# front_panel.net
KiCad netlist of a schematic drawn in EAGLE
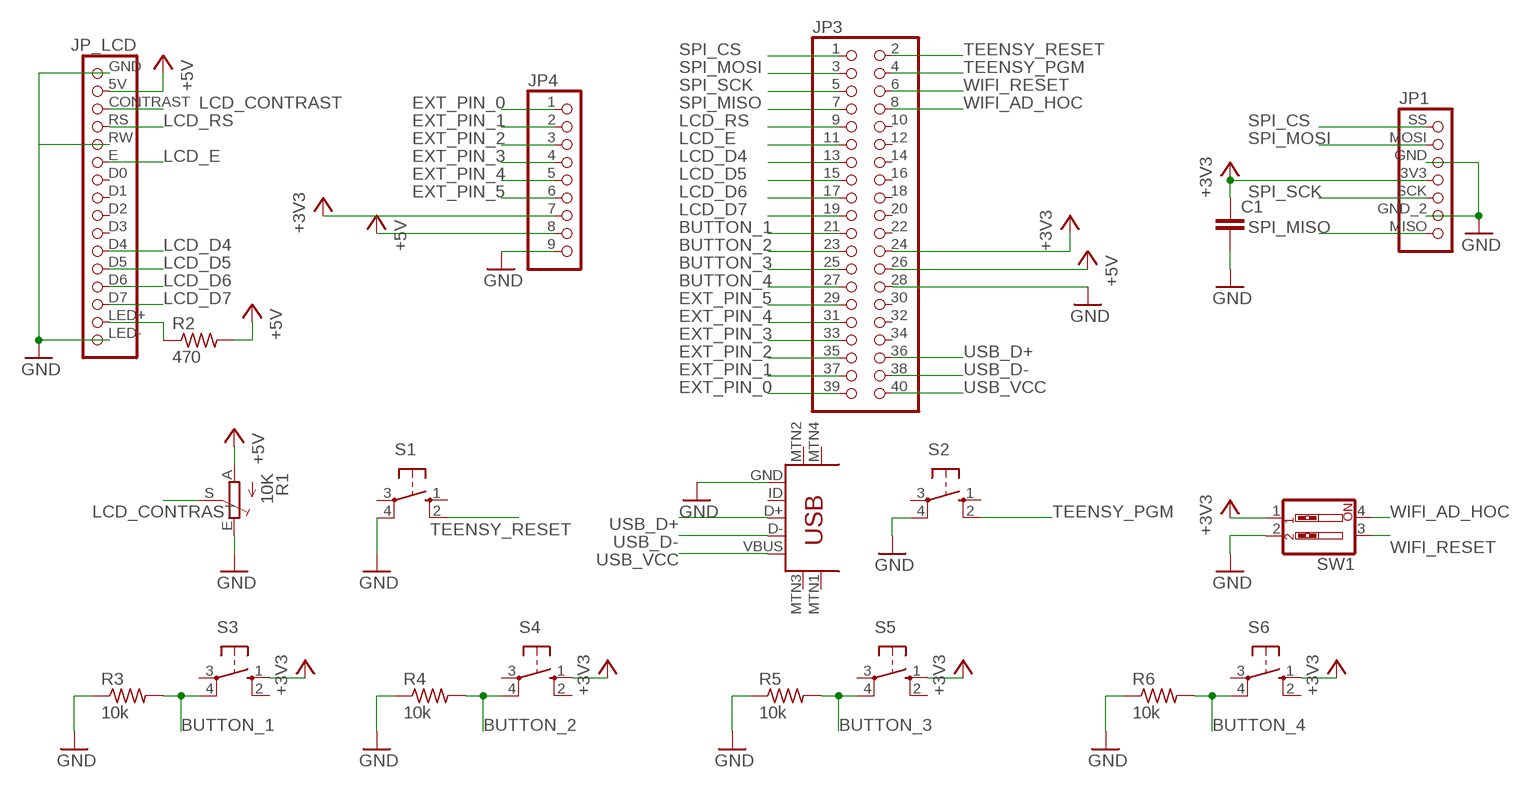
[diagram p0: schematic, sheet 1]

(export (version "E")
  (design (tool "Eeschema 10.0.6"))
  (components
    (comp (ref "C1")
      (value "0.1UF-50V-20%(PTH)KIT-EZ")
      (footprint "eagle-import:CAP-PTH-SMALL-KIT")
      (libsource (lib "eagle-import") (part "0.1UF-50V-20%(PTH)KIT-EZ"))
    )
    (comp (ref "JP1")
      (value "PINHD-1X7")
      (footprint "eagle-import:1X07")
      (libsource (lib "eagle-import") (part "PINHD-1X7"))
    )
    (comp (ref "JP3")
      (value "PINHD-2X20")
      (footprint "eagle-import:2X20")
      (libsource (lib "eagle-import") (part "PINHD-2X20"))
    )
    (comp (ref "JP4")
      (value "PINHD-1X9")
      (footprint "eagle-import:1X09")
      (libsource (lib "eagle-import") (part "PINHD-1X9"))
    )
    (comp (ref "JP_LCD")
      (value "PINHD-1X16")
      (footprint "eagle-import:1X16")
      (libsource (lib "eagle-import") (part "PINHD-1X16"))
    )
    (comp (ref "R1")
      (value "10K")
      (footprint "eagle-import:CA6V")
      (libsource (lib "eagle-import") (part "TRIM_EU-CA6V"))
    )
    (comp (ref "R2")
      (value "470")
      (footprint "eagle-import:0207_10")
      (libsource (lib "eagle-import") (part "R-US_0207/10"))
    )
    (comp (ref "R3")
      (value "10k")
      (footprint "eagle-import:0207_10")
      (libsource (lib "eagle-import") (part "R-US_0207/10"))
    )
    (comp (ref "R4")
      (value "10k")
      (footprint "eagle-import:0207_10")
      (libsource (lib "eagle-import") (part "R-US_0207/10"))
    )
    (comp (ref "R5")
      (value "10k")
      (footprint "eagle-import:0207_10")
      (libsource (lib "eagle-import") (part "R-US_0207/10"))
    )
    (comp (ref "R6")
      (value "10k")
      (footprint "eagle-import:0207_10")
      (libsource (lib "eagle-import") (part "R-US_0207/10"))
    )
    (comp (ref "S1")
      (value "10-XX")
      (footprint "eagle-import:B3F-10XX")
      (fields (field (name "MPN") "B3F-1000"))
      (libsource (lib "eagle-import") (part "10-XX"))
    )
    (comp (ref "S2")
      (value "10-XX")
      (footprint "eagle-import:B3F-10XX")
      (fields (field (name "MPN") "B3F-1000"))
      (libsource (lib "eagle-import") (part "10-XX"))
    )
    (comp (ref "S3")
      (value "10-XX")
      (footprint "eagle-import:B3F-10XX")
      (fields (field (name "MPN") "B3F-1000"))
      (libsource (lib "eagle-import") (part "10-XX"))
    )
    (comp (ref "S4")
      (value "10-XX")
      (footprint "eagle-import:B3F-10XX")
      (fields (field (name "MPN") "B3F-1000"))
      (libsource (lib "eagle-import") (part "10-XX"))
    )
    (comp (ref "S5")
      (value "10-XX")
      (footprint "eagle-import:B3F-10XX")
      (fields (field (name "MPN") "B3F-1000"))
      (libsource (lib "eagle-import") (part "10-XX"))
    )
    (comp (ref "S6")
      (value "10-XX")
      (footprint "eagle-import:B3F-10XX")
      (fields (field (name "MPN") "B3F-1000"))
      (libsource (lib "eagle-import") (part "10-XX"))
    )
    (comp (ref "SW1")
      (value "SW_DIP-2")
      (footprint "eagle-import:EDG-02")
      (libsource (lib "eagle-import") (part "SW_DIP-2"))
    )
    (comp (ref "U$1")
      (value "USB-MINIB-5PIN")
      (footprint "eagle-import:USB-MINIB")
      (libsource (lib "eagle-import") (part "USB-MINIB-5PIN"))
    )
  )
  (nets
    (net (code "1") (name "+3V3") (class "Default")
      (node (ref "C1") (pin "1") (pinfunction "1_1") (pintype "passive"))
      (node (ref "JP1") (pin "3V3") (pinfunction "4_3V3") (pintype "passive"))
      (node (ref "JP3") (pin "24") (pinfunction "24_24") (pintype "passive"))
      (node (ref "JP4") (pin "7") (pinfunction "7_7") (pintype "passive"))
      (node (ref "S3") (pin "1") (pinfunction "S_1") (pintype "passive"))
      (node (ref "S4") (pin "1") (pinfunction "S_1") (pintype "passive"))
      (node (ref "S5") (pin "1") (pinfunction "S_1") (pintype "passive"))
      (node (ref "S6") (pin "1") (pinfunction "S_1") (pintype "passive"))
      (node (ref "SW1") (pin "1") (pinfunction "1_1") (pintype "passive"))
    )
    (net (code "2") (name "+5V") (class "Default")
      (node (ref "JP3") (pin "26") (pinfunction "26_26") (pintype "passive"))
      (node (ref "JP4") (pin "8") (pinfunction "8_8") (pintype "passive"))
      (node (ref "JP_LCD") (pin "5V") (pinfunction "5V_5V") (pintype "passive"))
      (node (ref "R1") (pin "A") (pinfunction "A_A") (pintype "passive"))
      (node (ref "R2") (pin "2") (pinfunction "2_2") (pintype "passive"))
    )
    (net (code "3") (name "/BUTTON_1") (class "Default")
      (node (ref "JP3") (pin "21") (pinfunction "21_21") (pintype "passive"))
      (node (ref "R3") (pin "2") (pinfunction "2_2") (pintype "passive"))
      (node (ref "S3") (pin "4") (pinfunction "P1_4") (pintype "passive"))
    )
    (net (code "4") (name "/BUTTON_2") (class "Default")
      (node (ref "JP3") (pin "23") (pinfunction "23_23") (pintype "passive"))
      (node (ref "R4") (pin "2") (pinfunction "2_2") (pintype "passive"))
      (node (ref "S4") (pin "4") (pinfunction "P1_4") (pintype "passive"))
    )
    (net (code "5") (name "/BUTTON_3") (class "Default")
      (node (ref "JP3") (pin "25") (pinfunction "25_25") (pintype "passive"))
      (node (ref "R5") (pin "2") (pinfunction "2_2") (pintype "passive"))
      (node (ref "S5") (pin "4") (pinfunction "P1_4") (pintype "passive"))
    )
    (net (code "6") (name "/BUTTON_4") (class "Default")
      (node (ref "JP3") (pin "27") (pinfunction "27_27") (pintype "passive"))
      (node (ref "R6") (pin "2") (pinfunction "2_2") (pintype "passive"))
      (node (ref "S6") (pin "4") (pinfunction "P1_4") (pintype "passive"))
    )
    (net (code "7") (name "/EXT_PIN_0") (class "Default")
      (node (ref "JP3") (pin "39") (pinfunction "39_39") (pintype "passive"))
      (node (ref "JP4") (pin "1") (pinfunction "1_1") (pintype "passive"))
    )
    (net (code "8") (name "/EXT_PIN_1") (class "Default")
      (node (ref "JP3") (pin "37") (pinfunction "37_37") (pintype "passive"))
      (node (ref "JP4") (pin "2") (pinfunction "2_2") (pintype "passive"))
    )
    (net (code "9") (name "/EXT_PIN_2") (class "Default")
      (node (ref "JP3") (pin "35") (pinfunction "35_35") (pintype "passive"))
      (node (ref "JP4") (pin "3") (pinfunction "3_3") (pintype "passive"))
    )
    (net (code "10") (name "/EXT_PIN_3") (class "Default")
      (node (ref "JP3") (pin "33") (pinfunction "33_33") (pintype "passive"))
      (node (ref "JP4") (pin "4") (pinfunction "4_4") (pintype "passive"))
    )
    (net (code "11") (name "/EXT_PIN_4") (class "Default")
      (node (ref "JP3") (pin "31") (pinfunction "31_31") (pintype "passive"))
      (node (ref "JP4") (pin "5") (pinfunction "5_5") (pintype "passive"))
    )
    (net (code "12") (name "/EXT_PIN_5") (class "Default")
      (node (ref "JP3") (pin "29") (pinfunction "29_29") (pintype "passive"))
      (node (ref "JP4") (pin "6") (pinfunction "6_6") (pintype "passive"))
    )
    (net (code "13") (name "/LCD_CONTRAST") (class "Default")
      (node (ref "JP_LCD") (pin "CONTRAST") (pinfunction "CONTRAST_CONTRAST") (pintype "passive"))
      (node (ref "R1") (pin "S") (pinfunction "S_S") (pintype "passive"))
    )
    (net (code "14") (name "/LCD_D4") (class "Default")
      (node (ref "JP3") (pin "13") (pinfunction "13_13") (pintype "passive"))
      (node (ref "JP_LCD") (pin "D4") (pinfunction "D4_D4") (pintype "passive"))
    )
    (net (code "15") (name "/LCD_D5") (class "Default")
      (node (ref "JP3") (pin "15") (pinfunction "15_15") (pintype "passive"))
      (node (ref "JP_LCD") (pin "D5") (pinfunction "D5_D5") (pintype "passive"))
    )
    (net (code "16") (name "/LCD_D6") (class "Default")
      (node (ref "JP3") (pin "17") (pinfunction "17_17") (pintype "passive"))
      (node (ref "JP_LCD") (pin "D6") (pinfunction "D6_D6") (pintype "passive"))
    )
    (net (code "17") (name "/LCD_D7") (class "Default")
      (node (ref "JP3") (pin "19") (pinfunction "19_19") (pintype "passive"))
      (node (ref "JP_LCD") (pin "D7") (pinfunction "D7_D7") (pintype "passive"))
    )
    (net (code "18") (name "/LCD_E") (class "Default")
      (node (ref "JP3") (pin "11") (pinfunction "11_11") (pintype "passive"))
      (node (ref "JP_LCD") (pin "E") (pinfunction "E_E") (pintype "passive"))
    )
    (net (code "19") (name "/LCD_RS") (class "Default")
      (node (ref "JP3") (pin "9") (pinfunction "9_9") (pintype "passive"))
      (node (ref "JP_LCD") (pin "RS") (pinfunction "RS_RS") (pintype "passive"))
    )
    (net (code "20") (name "/SPI_CS") (class "Default")
      (node (ref "JP1") (pin "SS") (pinfunction "1_SS") (pintype "passive"))
      (node (ref "JP3") (pin "1") (pinfunction "1_1") (pintype "passive"))
    )
    (net (code "21") (name "/SPI_MISO") (class "Default")
      (node (ref "JP1") (pin "MISO") (pinfunction "7_MISO") (pintype "passive"))
      (node (ref "JP3") (pin "7") (pinfunction "7_7") (pintype "passive"))
    )
    (net (code "22") (name "/SPI_MOSI") (class "Default")
      (node (ref "JP1") (pin "MOSI") (pinfunction "2_MOSI") (pintype "passive"))
      (node (ref "JP3") (pin "3") (pinfunction "3_3") (pintype "passive"))
    )
    (net (code "23") (name "/SPI_SCK") (class "Default")
      (node (ref "JP1") (pin "SCK") (pinfunction "5_SCK") (pintype "passive"))
      (node (ref "JP3") (pin "5") (pinfunction "5_5") (pintype "passive"))
    )
    (net (code "24") (name "/TEENSY_PGM") (class "Default")
      (node (ref "JP3") (pin "4") (pinfunction "4_4") (pintype "passive"))
      (node (ref "S2") (pin "2") (pinfunction "S1_2") (pintype "passive"))
    )
    (net (code "25") (name "/TEENSY_RESET") (class "Default")
      (node (ref "JP3") (pin "2") (pinfunction "2_2") (pintype "passive"))
      (node (ref "S1") (pin "2") (pinfunction "S1_2") (pintype "passive"))
    )
    (net (code "26") (name "/USB_D+") (class "Default")
      (node (ref "JP3") (pin "36") (pinfunction "36_36") (pintype "passive"))
      (node (ref "U$1") (pin "D+") (pinfunction "D+_D+") (pintype "bidirectional"))
    )
    (net (code "27") (name "/USB_D-") (class "Default")
      (node (ref "JP3") (pin "38") (pinfunction "38_38") (pintype "passive"))
      (node (ref "U$1") (pin "D-") (pinfunction "D-_D-") (pintype "bidirectional"))
    )
    (net (code "28") (name "/USB_VCC") (class "Default")
      (node (ref "JP3") (pin "40") (pinfunction "40_40") (pintype "passive"))
      (node (ref "U$1") (pin "VBUS") (pinfunction "VBUS_VBUS") (pintype "bidirectional"))
    )
    (net (code "29") (name "/WIFI_AD_HOC") (class "Default")
      (node (ref "JP3") (pin "8") (pinfunction "8_8") (pintype "passive"))
      (node (ref "SW1") (pin "4") (pinfunction "4_4") (pintype "passive"))
    )
    (net (code "30") (name "/WIFI_RESET") (class "Default")
      (node (ref "JP3") (pin "6") (pinfunction "6_6") (pintype "passive"))
      (node (ref "SW1") (pin "3") (pinfunction "3_3") (pintype "passive"))
    )
    (net (code "31") (name "GND") (class "Default")
      (node (ref "C1") (pin "2") (pinfunction "2_2") (pintype "passive"))
      (node (ref "JP1") (pin "GND") (pinfunction "3_GND") (pintype "passive"))
      (node (ref "JP1") (pin "GND_2") (pinfunction "6_GND_2") (pintype "passive"))
      (node (ref "JP3") (pin "28") (pinfunction "28_28") (pintype "passive"))
      (node (ref "JP4") (pin "9") (pinfunction "9_9") (pintype "passive"))
      (node (ref "JP_LCD") (pin "GND") (pinfunction "GND_GND") (pintype "passive"))
      (node (ref "JP_LCD") (pin "LED-") (pinfunction "LED-_LED-") (pintype "passive"))
      (node (ref "JP_LCD") (pin "RW") (pinfunction "RW_RW") (pintype "passive"))
      (node (ref "R1") (pin "E") (pinfunction "E_E") (pintype "passive"))
      (node (ref "R3") (pin "1") (pinfunction "1_1") (pintype "passive"))
      (node (ref "R4") (pin "1") (pinfunction "1_1") (pintype "passive"))
      (node (ref "R5") (pin "1") (pinfunction "1_1") (pintype "passive"))
      (node (ref "R6") (pin "1") (pinfunction "1_1") (pintype "passive"))
      (node (ref "S1") (pin "4") (pinfunction "P1_4") (pintype "passive"))
      (node (ref "S2") (pin "4") (pinfunction "P1_4") (pintype "passive"))
      (node (ref "SW1") (pin "2") (pinfunction "2_2") (pintype "passive"))
      (node (ref "U$1") (pin "GND") (pinfunction "GND_GND") (pintype "bidirectional"))
    )
    (net (code "32") (name "Net-(JP_LCD-PadLED+)") (class "Default")
      (node (ref "JP_LCD") (pin "LED+") (pinfunction "LED+_LED+") (pintype "passive"))
      (node (ref "R2") (pin "1") (pinfunction "1_1") (pintype "passive"))
    )
    (net (code "33") (name "unconnected-(JP3-Pad10)") (class "Default")
      (node (ref "JP3") (pin "10") (pinfunction "10_10") (pintype "passive"))
    )
    (net (code "34") (name "unconnected-(JP3-Pad12)") (class "Default")
      (node (ref "JP3") (pin "12") (pinfunction "12_12") (pintype "passive"))
    )
    (net (code "35") (name "unconnected-(JP3-Pad14)") (class "Default")
      (node (ref "JP3") (pin "14") (pinfunction "14_14") (pintype "passive"))
    )
    (net (code "36") (name "unconnected-(JP3-Pad16)") (class "Default")
      (node (ref "JP3") (pin "16") (pinfunction "16_16") (pintype "passive"))
    )
    (net (code "37") (name "unconnected-(JP3-Pad18)") (class "Default")
      (node (ref "JP3") (pin "18") (pinfunction "18_18") (pintype "passive"))
    )
    (net (code "38") (name "unconnected-(JP3-Pad20)") (class "Default")
      (node (ref "JP3") (pin "20") (pinfunction "20_20") (pintype "passive"))
    )
    (net (code "39") (name "unconnected-(JP3-Pad22)") (class "Default")
      (node (ref "JP3") (pin "22") (pinfunction "22_22") (pintype "passive"))
    )
    (net (code "40") (name "unconnected-(JP3-Pad30)") (class "Default")
      (node (ref "JP3") (pin "30") (pinfunction "30_30") (pintype "passive"))
    )
    (net (code "41") (name "unconnected-(JP3-Pad32)") (class "Default")
      (node (ref "JP3") (pin "32") (pinfunction "32_32") (pintype "passive"))
    )
    (net (code "42") (name "unconnected-(JP3-Pad34)") (class "Default")
      (node (ref "JP3") (pin "34") (pinfunction "34_34") (pintype "passive"))
    )
    (net (code "43") (name "unconnected-(JP_LCD-PadD0)") (class "Default")
      (node (ref "JP_LCD") (pin "D0") (pinfunction "D0_D0") (pintype "passive"))
    )
    (net (code "44") (name "unconnected-(JP_LCD-PadD1)") (class "Default")
      (node (ref "JP_LCD") (pin "D1") (pinfunction "D1_D1") (pintype "passive"))
    )
    (net (code "45") (name "unconnected-(JP_LCD-PadD2)") (class "Default")
      (node (ref "JP_LCD") (pin "D2") (pinfunction "D2_D2") (pintype "passive"))
    )
    (net (code "46") (name "unconnected-(JP_LCD-PadD3)") (class "Default")
      (node (ref "JP_LCD") (pin "D3") (pinfunction "D3_D3") (pintype "passive"))
    )
    (net (code "47") (name "unconnected-(S1-P-Pad3)") (class "Default")
      (node (ref "S1") (pin "3") (pinfunction "P_3") (pintype "passive"))
    )
    (net (code "48") (name "unconnected-(S1-S-Pad1)") (class "Default")
      (node (ref "S1") (pin "1") (pinfunction "S_1") (pintype "passive"))
    )
    (net (code "49") (name "unconnected-(S2-P-Pad3)") (class "Default")
      (node (ref "S2") (pin "3") (pinfunction "P_3") (pintype "passive"))
    )
    (net (code "50") (name "unconnected-(S2-S-Pad1)") (class "Default")
      (node (ref "S2") (pin "1") (pinfunction "S_1") (pintype "passive"))
    )
    (net (code "51") (name "unconnected-(S3-P-Pad3)") (class "Default")
      (node (ref "S3") (pin "3") (pinfunction "P_3") (pintype "passive"))
    )
    (net (code "52") (name "unconnected-(S3-S1-Pad2)") (class "Default")
      (node (ref "S3") (pin "2") (pinfunction "S1_2") (pintype "passive"))
    )
    (net (code "53") (name "unconnected-(S4-P-Pad3)") (class "Default")
      (node (ref "S4") (pin "3") (pinfunction "P_3") (pintype "passive"))
    )
    (net (code "54") (name "unconnected-(S4-S1-Pad2)") (class "Default")
      (node (ref "S4") (pin "2") (pinfunction "S1_2") (pintype "passive"))
    )
    (net (code "55") (name "unconnected-(S5-P-Pad3)") (class "Default")
      (node (ref "S5") (pin "3") (pinfunction "P_3") (pintype "passive"))
    )
    (net (code "56") (name "unconnected-(S5-S1-Pad2)") (class "Default")
      (node (ref "S5") (pin "2") (pinfunction "S1_2") (pintype "passive"))
    )
    (net (code "57") (name "unconnected-(S6-P-Pad3)") (class "Default")
      (node (ref "S6") (pin "3") (pinfunction "P_3") (pintype "passive"))
    )
    (net (code "58") (name "unconnected-(S6-S1-Pad2)") (class "Default")
      (node (ref "S6") (pin "2") (pinfunction "S1_2") (pintype "passive"))
    )
    (net (code "59") (name "unconnected-(U$1-MTN1-PadMTN3)") (class "Default")
      (node (ref "U$1") (pin "MTN3") (pinfunction "MTN1_MTN3") (pintype "bidirectional"))
    )
    (net (code "60") (name "unconnected-(U$1-MTN2-PadMTN1)") (class "Default")
      (node (ref "U$1") (pin "MTN1") (pinfunction "MTN2_MTN1") (pintype "bidirectional"))
    )
    (net (code "61") (name "unconnected-(U$1-MTN3-PadMTN2)") (class "Default")
      (node (ref "U$1") (pin "MTN2") (pinfunction "MTN3_MTN2") (pintype "bidirectional"))
    )
    (net (code "62") (name "unconnected-(U$1-PadID)") (class "Default")
      (node (ref "U$1") (pin "ID") (pinfunction "ID_ID") (pintype "bidirectional"))
    )
    (net (code "63") (name "unconnected-(U$1-PadMTN4)") (class "Default")
      (node (ref "U$1") (pin "MTN4") (pinfunction "MTN4_MTN4") (pintype "bidirectional"))
    )
  )
)
